# 6.net
KiCad netlist of a schematic drawn in Altium Designer
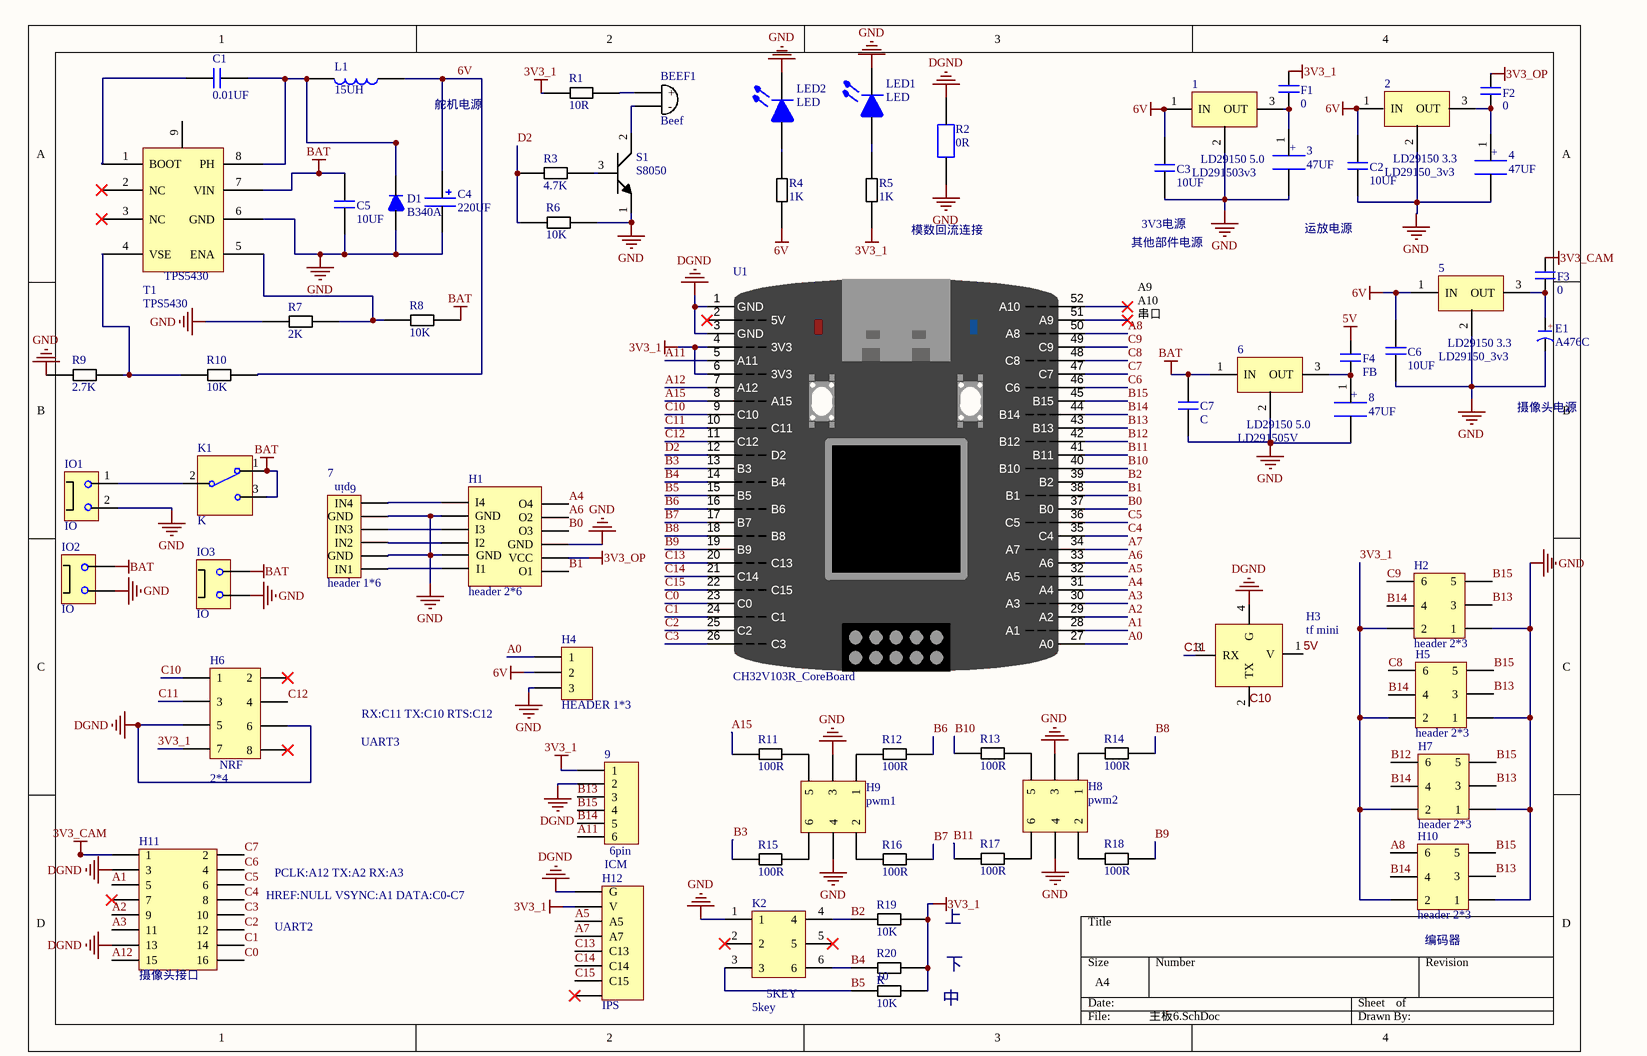
[diagram p0: 主板6.SchDoc]

(export (version "E")
  (design (tool "Eeschema 10.0.6"))
  (components
    (comp (ref "1")
      (value "LD291503v3")
      (footprint "LD29150")
      (description "5v转压")
      (libsource (lib "主板4") (part "LD291505V"))
    )
    (comp (ref "2")
      (value "LD29150_3v3")
      (footprint "LD29150")
      (description "转压3v3")
      (libsource (lib "主板4") (part "LD29150_3v3"))
    )
    (comp (ref "3") (value "47UF") (footprint "CD A(3216)") (libsource (lib "主板4") (part "钽电容")))
    (comp (ref "4") (value "47UF") (footprint "CD A(3216)") (libsource (lib "主板4") (part "钽电容")))
    (comp (ref "5")
      (value "LD29150_3v3")
      (footprint "LD29150")
      (description "转压3v3")
      (libsource (lib "主板4") (part "LD29150_3v3"))
    )
    (comp (ref "6")
      (value "LD291505V")
      (footprint "LD29150")
      (description "5v转压")
      (libsource (lib "主板6") (part "LD291505V"))
    )
    (comp (ref "7")
      (value "header 1*6")
      (footprint "HDR2.54-LI-6P")
      (description "ICM")
      (libsource (lib "") (part "header 1*6_1"))
    )
    (comp (ref "8") (value "47UF") (footprint "CD A(3216)") (libsource (lib "主板4") (part "钽电容")))
    (comp (ref "9") (value "ICM") (footprint "HDR2.54-LI-6P") (libsource (lib "主板4") (part "header 1*6")))
    (comp (ref "10") (value "10K") (footprint "0603-R") (description "电阻") (libsource (lib "主板4") (part "R")))
    (comp (ref "BEEF1")
      (value "Beef")
      (footprint "BEEF")
      (description "蜂鸣器")
      (libsource (lib "主板4") (part "Beef"))
    )
    (comp (ref "C1")
      (value "0.01UF")
      (footprint "C 0603_L")
      (description "陶瓷电容")
      (libsource (lib "主板4") (part "C"))
    )
    (comp (ref "C2")
      (value "10UF")
      (footprint "C 0603_L")
      (description "陶瓷电容")
      (libsource (lib "主板4") (part "C"))
    )
    (comp (ref "C3")
      (value "10UF")
      (footprint "C 0603_L")
      (description "陶瓷电容")
      (libsource (lib "主板4") (part "C"))
    )
    (comp (ref "C4")
      (value "220UF")
      (footprint "CAP 2.5*6.3*7")
      (description "有极电容")
      (libsource (lib "主板4") (part "C+"))
    )
    (comp (ref "C5")
      (value "10UF")
      (footprint "C 0603_L")
      (description "陶瓷电容")
      (libsource (lib "主板4") (part "C"))
    )
    (comp (ref "C6")
      (value "10UF")
      (footprint "C 0603_L")
      (description "陶瓷电容")
      (libsource (lib "主板4") (part "C"))
    )
    (comp (ref "C7")
      (value "C")
      (footprint "C 0603_L")
      (description "陶瓷电容")
      (libsource (lib "主板6") (part "C"))
    )
    (comp (ref "D1") (value "B340A") (footprint "SMA") (description "二极管") (libsource (lib "主板4") (part "D")))
    (comp (ref "E1")
      (value "A476C")
      (footprint "CD A(3216)")
      (description "贴片钽电容")
      (fields (field (name "版权归属") "源创客"))
      (libsource (lib "3.1   - 电阻-电容-电感") (part "C-CD"))
    )
    (comp (ref "F1")
      (value "0")
      (footprint "0603-C")
      (description "0欧磁珠")
      (libsource (lib "主板4") (part "FB"))
    )
    (comp (ref "F2")
      (value "0")
      (footprint "0603-C")
      (description "0欧磁珠")
      (libsource (lib "主板4") (part "FB"))
    )
    (comp (ref "F3")
      (value "0")
      (footprint "0603-C")
      (description "0欧磁珠")
      (libsource (lib "主板4") (part "FB"))
    )
    (comp (ref "F4")
      (value "FB")
      (footprint "0603-C")
      (description "0欧磁珠")
      (libsource (lib "主板6") (part "FB"))
    )
    (comp (ref "H1")
      (value "header 2*6")
      (footprint "OP")
      (description "运放接口")
      (libsource (lib "主板4") (part "header 2*6"))
    )
    (comp (ref "H2")
      (value "header 2*3")
      (footprint "HDR2.54-LI-2x3P")
      (description "编码器，PWM")
      (libsource (lib "") (part "header 2*3_1"))
    )
    (comp (ref "H3")
      (value "tf mini")
      (footprint "GH1.25")
      (description "TF MINI")
      (libsource (lib "主板6") (part "HEADER 4"))
    )
    (comp (ref "H4")
      (value "HEADER 1*3")
      (footprint "HDR2.54-LI-3P")
      (description "舵机")
      (libsource (lib "主板4") (part "HEADER 1*3"))
    )
    (comp (ref "H5")
      (value "header 2*3")
      (footprint "HDR2.54-LI-2x3P")
      (description "编码器，PWM")
      (libsource (lib "") (part "header 2*3_1"))
    )
    (comp (ref "H6")
      (value "2*4")
      (footprint "HDR2.54-LI-2x4P")
      (description "NRF")
      (libsource (lib "主板4") (part "2*4"))
    )
    (comp (ref "H7")
      (value "header 2*3")
      (footprint "HDR2.54-LI-2x3P")
      (description "编码器，PWM")
      (libsource (lib "") (part "header 2*3_1"))
    )
    (comp (ref "H8")
      (value "pwm2")
      (footprint "HDR2.54-LI-2x3P")
      (description "编码器，PWM")
      (libsource (lib "主板4") (part "header 2*3"))
    )
    (comp (ref "H9")
      (value "pwm1")
      (footprint "HDR2.54-LI-2x3P")
      (description "编码器，PWM")
      (libsource (lib "主板4") (part "header 2*3"))
    )
    (comp (ref "H10")
      (value "header 2*3")
      (footprint "HDR2.54-LI-2x3P")
      (description "编码器，PWM")
      (libsource (lib "") (part "header 2*3_1"))
    )
    (comp (ref "H11")
      (value "摄像头接口")
      (footprint "HDR2.54-LI-2x8P")
      (libsource (lib "主板4") (part "Header 2*8"))
    )
    (comp (ref "H12")
      (value "IPS")
      (footprint "HDR2.54-M-LI-8P")
      (description "屏幕")
      (libsource (lib "主板5") (part "HEADER 8"))
    )
    (comp (ref "IO1") (value "IO") (footprint "XT30") (description "接口") (libsource (lib "主板4") (part "IO")))
    (comp (ref "IO2") (value "IO") (footprint "XT30") (description "接口") (libsource (lib "") (part "IO_1")))
    (comp (ref "IO3") (value "IO") (footprint "XT30") (description "接口") (libsource (lib "") (part "IO_1")))
    (comp (ref "K1")
      (value "K")
      (footprint "SW-SPDT-3A250V")
      (description "开关")
      (libsource (lib "主板4") (part "K"))
    )
    (comp (ref "K2")
      (value "5key")
      (footprint "5KEY")
      (description "5Key")
      (libsource (lib "主板4") (part "5key"))
    )
    (comp (ref "L1")
      (value "15UH")
      (footprint "L-SMD-7")
      (description "电感")
      (libsource (lib "主板4") (part "L"))
    )
    (comp (ref "LED1") (value "LED") (footprint "0603-LED-R") (libsource (lib "主板4") (part "LED")))
    (comp (ref "LED2") (value "LED") (footprint "0603-LED-R") (libsource (lib "主板4") (part "LED")))
    (comp (ref "R1") (value "10R") (footprint "0603-R") (description "电阻") (libsource (lib "主板4") (part "R")))
    (comp (ref "R2")
      (value "0R")
      (footprint "0603-C")
      (description "0欧电阻")
      (libsource (lib "主板4") (part "R0"))
    )
    (comp (ref "R3")
      (value "4.7K")
      (footprint "0603-R")
      (description "电阻")
      (libsource (lib "主板4") (part "R"))
    )
    (comp (ref "R4") (value "1K") (footprint "0603-R") (description "电阻") (libsource (lib "主板4") (part "R")))
    (comp (ref "R5") (value "1K") (footprint "0603-R") (description "电阻") (libsource (lib "主板4") (part "R")))
    (comp (ref "R6") (value "10K") (footprint "0603-R") (description "电阻") (libsource (lib "主板4") (part "R")))
    (comp (ref "R7") (value "2K") (footprint "0603-R") (description "电阻") (libsource (lib "主板4") (part "R")))
    (comp (ref "R8") (value "10K") (footprint "0603-R") (description "电阻") (libsource (lib "主板4") (part "R")))
    (comp (ref "R9")
      (value "2.7K")
      (footprint "0603-R")
      (description "电阻")
      (libsource (lib "主板4") (part "R"))
    )
    (comp (ref "R10")
      (value "10K")
      (footprint "0603-R")
      (description "电阻")
      (libsource (lib "主板4") (part "R"))
    )
    (comp (ref "R11")
      (value "100R")
      (footprint "0603-R")
      (description "电阻")
      (libsource (lib "主板4") (part "R"))
    )
    (comp (ref "R12")
      (value "100R")
      (footprint "0603-R")
      (description "电阻")
      (libsource (lib "主板4") (part "R"))
    )
    (comp (ref "R13")
      (value "100R")
      (footprint "0603-R")
      (description "电阻")
      (libsource (lib "主板4") (part "R"))
    )
    (comp (ref "R14")
      (value "100R")
      (footprint "0603-R")
      (description "电阻")
      (libsource (lib "主板4") (part "R"))
    )
    (comp (ref "R15")
      (value "100R")
      (footprint "0603-R")
      (description "电阻")
      (libsource (lib "主板4") (part "R"))
    )
    (comp (ref "R16")
      (value "100R")
      (footprint "0603-R")
      (description "电阻")
      (libsource (lib "主板4") (part "R"))
    )
    (comp (ref "R17")
      (value "100R")
      (footprint "0603-R")
      (description "电阻")
      (libsource (lib "主板4") (part "R"))
    )
    (comp (ref "R18")
      (value "100R")
      (footprint "0603-R")
      (description "电阻")
      (libsource (lib "主板4") (part "R"))
    )
    (comp (ref "R19")
      (value "10K")
      (footprint "0603-R")
      (description "电阻")
      (libsource (lib "主板4") (part "R"))
    )
    (comp (ref "R20") (value "R") (footprint "0603-R") (description "电阻") (libsource (lib "主板4") (part "R")))
    (comp (ref "S1")
      (value "S8050")
      (footprint "SOT-23-3_L2.9-W1.3-P1.90-LS2.4-BR - duplicate")
      (description "三极管")
      (libsource (lib "主板4") (part "S8050"))
    )
    (comp (ref "T1")
      (value "TPS5430")
      (footprint "TPS5430")
      (description "转压8转6v")
      (libsource (lib "主板4") (part "TPS5430"))
    )
    (comp (ref "U1")
      (value "CH32V103R_CoreBoard")
      (footprint "CH32V103R_CoreBoard")
      (description "逐飞科技 CH32V103R核心板")
      (libsource (lib "主板4") (part "CH32V103R_CoreBoard"))
    )
  )
  (nets
    (net (code "1") (name "/A0") (class "Default")
      (node (ref "H4") (pin "1") (pinfunction "1_1") (pintype "passive"))
      (node (ref "U1") (pin "27") (pinfunction "A0_27") (pintype "passive"))
    )
    (net (code "2") (name "/A1") (class "Default")
      (node (ref "H11") (pin "5") (pinfunction "5_5") (pintype "passive"))
      (node (ref "U1") (pin "28") (pinfunction "A1_28") (pintype "passive"))
    )
    (net (code "3") (name "/A2") (class "Default")
      (node (ref "H11") (pin "9") (pinfunction "9_9") (pintype "passive"))
      (node (ref "U1") (pin "29") (pinfunction "A2_29") (pintype "passive"))
    )
    (net (code "4") (name "/A3") (class "Default")
      (node (ref "H11") (pin "11") (pinfunction "11_11") (pintype "passive"))
      (node (ref "U1") (pin "30") (pinfunction "A3_30") (pintype "passive"))
    )
    (net (code "5") (name "/A4") (class "Default")
      (node (ref "H1") (pin "12") (pinfunction "O4_12") (pintype "passive"))
      (node (ref "U1") (pin "31") (pinfunction "A4_31") (pintype "passive"))
    )
    (net (code "6") (name "/A5") (class "Default")
      (node (ref "H12") (pin "3") (pinfunction "A5_3") (pintype "passive"))
      (node (ref "U1") (pin "32") (pinfunction "A5_32") (pintype "passive"))
    )
    (net (code "7") (name "/A6") (class "Default")
      (node (ref "H1") (pin "10") (pinfunction "O2_10") (pintype "passive"))
      (node (ref "U1") (pin "33") (pinfunction "A6_33") (pintype "passive"))
    )
    (net (code "8") (name "/A7") (class "Default")
      (node (ref "H12") (pin "4") (pinfunction "A7_4") (pintype "passive"))
      (node (ref "U1") (pin "34") (pinfunction "A7_34") (pintype "passive"))
    )
    (net (code "9") (name "/A8") (class "Default")
      (node (ref "H10") (pin "6") (pinfunction "6_6") (pintype "passive"))
      (node (ref "U1") (pin "50") (pinfunction "A8_50") (pintype "passive"))
    )
    (net (code "10") (name "/A11") (class "Default")
      (node (ref "9") (pin "6") (pinfunction "6_6") (pintype "passive"))
      (node (ref "U1") (pin "5") (pinfunction "A11_5") (pintype "passive"))
    )
    (net (code "11") (name "/A12") (class "Default")
      (node (ref "H11") (pin "15") (pinfunction "15_15") (pintype "passive"))
      (node (ref "U1") (pin "7") (pinfunction "A12_7") (pintype "passive"))
    )
    (net (code "12") (name "/A15") (class "Default")
      (node (ref "R11") (pin "1") (pinfunction "1_1") (pintype "passive"))
      (node (ref "U1") (pin "8") (pinfunction "A15_8") (pintype "passive"))
    )
    (net (code "13") (name "/B0") (class "Default")
      (node (ref "H1") (pin "11") (pinfunction "O3_11") (pintype "passive"))
      (node (ref "U1") (pin "37") (pinfunction "B0_37") (pintype "passive"))
    )
    (net (code "14") (name "/B1") (class "Default")
      (node (ref "H1") (pin "7") (pinfunction "O1_7") (pintype "passive"))
      (node (ref "U1") (pin "38") (pinfunction "B1_38") (pintype "passive"))
    )
    (net (code "15") (name "/B2") (class "Default")
      (node (ref "K2") (pin "4") (pinfunction "4_4") (pintype "passive"))
      (node (ref "R19") (pin "1") (pinfunction "1_1") (pintype "passive"))
      (node (ref "U1") (pin "39") (pinfunction "B2_39") (pintype "passive"))
    )
    (net (code "16") (name "/B3") (class "Default")
      (node (ref "R15") (pin "1") (pinfunction "1_1") (pintype "passive"))
      (node (ref "U1") (pin "13") (pinfunction "B3_13") (pintype "passive"))
    )
    (net (code "17") (name "/B4") (class "Default")
      (node (ref "K2") (pin "6") (pinfunction "6_6") (pintype "passive"))
      (node (ref "R20") (pin "1") (pinfunction "1_1") (pintype "passive"))
      (node (ref "U1") (pin "14") (pinfunction "B4_14") (pintype "passive"))
    )
    (net (code "18") (name "/B5") (class "Default")
      (node (ref "10") (pin "1") (pinfunction "1_1") (pintype "passive"))
      (node (ref "K2") (pin "3") (pinfunction "3_3") (pintype "passive"))
      (node (ref "U1") (pin "15") (pinfunction "B5_15") (pintype "passive"))
    )
    (net (code "19") (name "/B6") (class "Default")
      (node (ref "R12") (pin "2") (pinfunction "2_2") (pintype "passive"))
      (node (ref "U1") (pin "16") (pinfunction "B6_16") (pintype "passive"))
    )
    (net (code "20") (name "/B7") (class "Default")
      (node (ref "R16") (pin "2") (pinfunction "2_2") (pintype "passive"))
      (node (ref "U1") (pin "17") (pinfunction "B7_17") (pintype "passive"))
    )
    (net (code "21") (name "/B8") (class "Default")
      (node (ref "R14") (pin "2") (pinfunction "2_2") (pintype "passive"))
      (node (ref "U1") (pin "18") (pinfunction "B8_18") (pintype "passive"))
    )
    (net (code "22") (name "/B9") (class "Default")
      (node (ref "R18") (pin "2") (pinfunction "2_2") (pintype "passive"))
      (node (ref "U1") (pin "19") (pinfunction "B9_19") (pintype "passive"))
    )
    (net (code "23") (name "/B10") (class "Default")
      (node (ref "R13") (pin "1") (pinfunction "1_1") (pintype "passive"))
      (node (ref "U1") (pin "40") (pinfunction "B10_40") (pintype "passive"))
    )
    (net (code "24") (name "/B11") (class "Default")
      (node (ref "R17") (pin "1") (pinfunction "1_1") (pintype "passive"))
      (node (ref "U1") (pin "41") (pinfunction "B11_41") (pintype "passive"))
    )
    (net (code "25") (name "/B12") (class "Default")
      (node (ref "H7") (pin "6") (pinfunction "6_6") (pintype "passive"))
      (node (ref "U1") (pin "42") (pinfunction "B12_42") (pintype "passive"))
    )
    (net (code "26") (name "/B13") (class "Default")
      (node (ref "9") (pin "3") (pinfunction "3_3") (pintype "passive"))
      (node (ref "H10") (pin "3") (pinfunction "3_3") (pintype "passive"))
      (node (ref "H2") (pin "3") (pinfunction "3_3") (pintype "passive"))
      (node (ref "H5") (pin "3") (pinfunction "3_3") (pintype "passive"))
      (node (ref "H7") (pin "3") (pinfunction "3_3") (pintype "passive"))
      (node (ref "U1") (pin "43") (pinfunction "B13_43") (pintype "passive"))
    )
    (net (code "27") (name "/B14") (class "Default")
      (node (ref "9") (pin "5") (pinfunction "5_5") (pintype "passive"))
      (node (ref "H10") (pin "4") (pinfunction "4_4") (pintype "passive"))
      (node (ref "H2") (pin "4") (pinfunction "4_4") (pintype "passive"))
      (node (ref "H5") (pin "4") (pinfunction "4_4") (pintype "passive"))
      (node (ref "H7") (pin "4") (pinfunction "4_4") (pintype "passive"))
      (node (ref "U1") (pin "44") (pinfunction "B14_44") (pintype "passive"))
    )
    (net (code "28") (name "/B15") (class "Default")
      (node (ref "9") (pin "4") (pinfunction "4_4") (pintype "passive"))
      (node (ref "H10") (pin "5") (pinfunction "5_5") (pintype "passive"))
      (node (ref "H2") (pin "5") (pinfunction "5_5") (pintype "passive"))
      (node (ref "H5") (pin "5") (pinfunction "5_5") (pintype "passive"))
      (node (ref "H7") (pin "5") (pinfunction "5_5") (pintype "passive"))
      (node (ref "U1") (pin "45") (pinfunction "B15_45") (pintype "passive"))
    )
    (net (code "29") (name "/C0") (class "Default")
      (node (ref "H11") (pin "16") (pinfunction "16_16") (pintype "passive"))
      (node (ref "U1") (pin "23") (pinfunction "C0_23") (pintype "passive"))
    )
    (net (code "30") (name "/C1") (class "Default")
      (node (ref "H11") (pin "14") (pinfunction "14_14") (pintype "passive"))
      (node (ref "U1") (pin "24") (pinfunction "C1_24") (pintype "passive"))
    )
    (net (code "31") (name "/C2") (class "Default")
      (node (ref "H11") (pin "12") (pinfunction "12_12") (pintype "passive"))
      (node (ref "U1") (pin "25") (pinfunction "C2_25") (pintype "passive"))
    )
    (net (code "32") (name "/C3") (class "Default")
      (node (ref "H11") (pin "10") (pinfunction "10_10") (pintype "passive"))
      (node (ref "U1") (pin "26") (pinfunction "C3_26") (pintype "passive"))
    )
    (net (code "33") (name "/C4") (class "Default")
      (node (ref "H11") (pin "8") (pinfunction "8_8") (pintype "passive"))
      (node (ref "U1") (pin "35") (pinfunction "C4_35") (pintype "passive"))
    )
    (net (code "34") (name "/C5") (class "Default")
      (node (ref "H11") (pin "6") (pinfunction "6_6") (pintype "passive"))
      (node (ref "U1") (pin "36") (pinfunction "C5_36") (pintype "passive"))
    )
    (net (code "35") (name "/C6") (class "Default")
      (node (ref "H11") (pin "4") (pinfunction "4_4") (pintype "passive"))
      (node (ref "U1") (pin "46") (pinfunction "C6_46") (pintype "passive"))
    )
    (net (code "36") (name "/C7") (class "Default")
      (node (ref "H11") (pin "2") (pinfunction "2_2") (pintype "passive"))
      (node (ref "U1") (pin "47") (pinfunction "C7_47") (pintype "passive"))
    )
    (net (code "37") (name "/C8") (class "Default")
      (node (ref "H5") (pin "6") (pinfunction "6_6") (pintype "passive"))
      (node (ref "U1") (pin "48") (pinfunction "C8_48") (pintype "passive"))
    )
    (net (code "38") (name "/C9") (class "Default")
      (node (ref "H2") (pin "6") (pinfunction "6_6") (pintype "passive"))
      (node (ref "U1") (pin "49") (pinfunction "C9_49") (pintype "passive"))
    )
    (net (code "39") (name "/C10") (class "Default")
      (node (ref "H3") (pin "2") (pinfunction "TX_2") (pintype "passive"))
      (node (ref "H6") (pin "1") (pinfunction "1_1") (pintype "passive"))
      (node (ref "U1") (pin "9") (pinfunction "C10_9") (pintype "passive"))
    )
    (net (code "40") (name "/C11") (class "Default")
      (node (ref "H3") (pin "3") (pinfunction "RX_3") (pintype "passive"))
      (node (ref "H6") (pin "3") (pinfunction "3_3") (pintype "passive"))
      (node (ref "U1") (pin "10") (pinfunction "C11_10") (pintype "passive"))
    )
    (net (code "41") (name "/C12") (class "Default")
      (node (ref "H6") (pin "4") (pinfunction "4_4") (pintype "passive"))
      (node (ref "U1") (pin "11") (pinfunction "C12_11") (pintype "passive"))
    )
    (net (code "42") (name "/C13") (class "Default")
      (node (ref "H12") (pin "5") (pinfunction "C13_5") (pintype "passive"))
      (node (ref "U1") (pin "20") (pinfunction "C13_20") (pintype "passive"))
    )
    (net (code "43") (name "/C14") (class "Default")
      (node (ref "H12") (pin "6") (pinfunction "C14_6") (pintype "passive"))
      (node (ref "U1") (pin "21") (pinfunction "C14_21") (pintype "passive"))
    )
    (net (code "44") (name "/C15") (class "Default")
      (node (ref "H12") (pin "7") (pinfunction "C15_7") (pintype "passive"))
      (node (ref "U1") (pin "22") (pinfunction "C15_22") (pintype "passive"))
    )
    (net (code "45") (name "/D2") (class "Default")
      (node (ref "R3") (pin "1") (pinfunction "1_1") (pintype "passive"))
      (node (ref "R6") (pin "1") (pinfunction "1_1") (pintype "passive"))
      (node (ref "U1") (pin "12") (pinfunction "D2_12") (pintype "passive"))
    )
    (net (code "46") (name "3V3_1") (class "Default")
      (node (ref "10") (pin "2") (pinfunction "2_2") (pintype "passive"))
      (node (ref "9") (pin "1") (pinfunction "1_1") (pintype "passive"))
      (node (ref "F1") (pin "2") (pinfunction "2_2") (pintype "passive"))
      (node (ref "H10") (pin "2") (pinfunction "2_2") (pintype "passive"))
      (node (ref "H12") (pin "2") (pinfunction "V_2") (pintype "passive"))
      (node (ref "H2") (pin "2") (pinfunction "2_2") (pintype "passive"))
      (node (ref "H5") (pin "2") (pinfunction "2_2") (pintype "passive"))
      (node (ref "H6") (pin "7") (pinfunction "7_7") (pintype "passive"))
      (node (ref "H7") (pin "2") (pinfunction "2_2") (pintype "passive"))
      (node (ref "R1") (pin "1") (pinfunction "1_1") (pintype "passive"))
      (node (ref "R19") (pin "2") (pinfunction "2_2") (pintype "passive"))
      (node (ref "R20") (pin "2") (pinfunction "2_2") (pintype "passive"))
      (node (ref "R5") (pin "1") (pinfunction "1_1") (pintype "passive"))
      (node (ref "U1") (pin "4") (pinfunction "3V3_4") (pintype "passive"))
      (node (ref "U1") (pin "6") (pinfunction "3V3_6") (pintype "passive"))
    )
    (net (code "47") (name "3V3_CAM") (class "Default")
      (node (ref "F3") (pin "1") (pinfunction "1_1") (pintype "passive"))
      (node (ref "H11") (pin "1") (pinfunction "1_1") (pintype "passive"))
    )
    (net (code "48") (name "3V3_OP") (class "Default")
      (node (ref "F2") (pin "1") (pinfunction "1_1") (pintype "passive"))
      (node (ref "H1") (pin "8") (pinfunction "VCC_8") (pintype "passive"))
    )
    (net (code "49") (name "5V") (class "Default")
      (node (ref "F4") (pin "2") (pinfunction "2_2") (pintype "passive"))
      (node (ref "H3") (pin "1") (pinfunction "V_1") (pintype "passive"))
    )
    (net (code "50") (name "6V") (class "Default")
      (node (ref "1") (pin "1") (pinfunction "IN_1") (pintype "passive"))
      (node (ref "2") (pin "1") (pinfunction "IN_1") (pintype "passive"))
      (node (ref "5") (pin "1") (pinfunction "IN_1") (pintype "passive"))
      (node (ref "C2") (pin "2") (pinfunction "2_2") (pintype "passive"))
      (node (ref "C3") (pin "1") (pinfunction "1_1") (pintype "passive"))
      (node (ref "C4") (pin "1") (pinfunction "1_1") (pintype "passive"))
      (node (ref "C6") (pin "2") (pinfunction "2_2") (pintype "passive"))
      (node (ref "H4") (pin "2") (pinfunction "2_2") (pintype "passive"))
      (node (ref "L1") (pin "2") (pinfunction "2_2") (pintype "passive"))
      (node (ref "R10") (pin "2") (pinfunction "2_2") (pintype "passive"))
      (node (ref "R4") (pin "1") (pinfunction "1_1") (pintype "passive"))
    )
    (net (code "51") (name "BAT") (class "Default")
      (node (ref "6") (pin "1") (pinfunction "IN_1") (pintype "passive"))
      (node (ref "C5") (pin "2") (pinfunction "2_2") (pintype "passive"))
      (node (ref "C7") (pin "2") (pinfunction "2_2") (pintype "passive"))
      (node (ref "IO2") (pin "1") (pinfunction "1_1") (pintype "passive"))
      (node (ref "IO3") (pin "1") (pinfunction "1_1") (pintype "passive"))
      (node (ref "K1") (pin "1") (pinfunction "1_1") (pintype "passive"))
      (node (ref "K1") (pin "3") (pinfunction "3_3") (pintype "passive"))
      (node (ref "R8") (pin "2") (pinfunction "2_2") (pintype "passive"))
      (node (ref "T1") (pin "7") (pinfunction "VIN_7") (pintype "passive"))
    )
    (net (code "52") (name "DGND") (class "Default")
      (node (ref "9") (pin "2") (pinfunction "2_2") (pintype "passive"))
      (node (ref "H11") (pin "13") (pinfunction "13_13") (pintype "passive"))
      (node (ref "H11") (pin "3") (pinfunction "3_3") (pintype "passive"))
      (node (ref "H12") (pin "1") (pinfunction "G_1") (pintype "passive"))
      (node (ref "H3") (pin "4") (pinfunction "G_4") (pintype "passive"))
      (node (ref "H6") (pin "5") (pinfunction "5_5") (pintype "passive"))
      (node (ref "H6") (pin "6") (pinfunction "6_6") (pintype "passive"))
      (node (ref "R2") (pin "2") (pinfunction "2_2") (pintype "passive"))
      (node (ref "U1") (pin "1") (pinfunction "GND_1") (pintype "passive"))
      (node (ref "U1") (pin "3") (pinfunction "GND_3") (pintype "passive"))
    )
    (net (code "53") (name "GND") (class "Default")
      (node (ref "1") (pin "2") (pinfunction "GND_2") (pintype "passive"))
      (node (ref "2") (pin "2") (pinfunction "GND_2") (pintype "passive"))
      (node (ref "3") (pin "2") (pinfunction "2_2") (pintype "passive"))
      (node (ref "4") (pin "2") (pinfunction "2_2") (pintype "passive"))
      (node (ref "5") (pin "2") (pinfunction "GND_2") (pintype "passive"))
      (node (ref "6") (pin "2") (pinfunction "GND_2") (pintype "passive"))
      (node (ref "7") (pin "2") (pinfunction "GND_2") (pintype "passive"))
      (node (ref "7") (pin "5") (pinfunction "GND_5") (pintype "passive"))
      (node (ref "8") (pin "2") (pinfunction "2_2") (pintype "passive"))
      (node (ref "C2") (pin "1") (pinfunction "1_1") (pintype "passive"))
      (node (ref "C3") (pin "2") (pinfunction "2_2") (pintype "passive"))
      (node (ref "C4") (pin "2") (pinfunction "2_2") (pintype "passive"))
      (node (ref "C5") (pin "1") (pinfunction "1_1") (pintype "passive"))
      (node (ref "C6") (pin "1") (pinfunction "1_1") (pintype "passive"))
      (node (ref "C7") (pin "1") (pinfunction "1_1") (pintype "passive"))
      (node (ref "D1") (pin "1") (pinfunction "A_1") (pintype "passive"))
      (node (ref "E1") (pin "2") (pinfunction "K_2") (pintype "passive"))
      (node (ref "H1") (pin "2") (pinfunction "GND_2") (pintype "passive"))
      (node (ref "H1") (pin "5") (pinfunction "GND_5") (pintype "passive"))
      (node (ref "H1") (pin "9") (pinfunction "GND_9") (pintype "passive"))
      (node (ref "H10") (pin "1") (pinfunction "1_1") (pintype "passive"))
      (node (ref "H2") (pin "1") (pinfunction "1_1") (pintype "passive"))
      (node (ref "H4") (pin "3") (pinfunction "3_3") (pintype "passive"))
      (node (ref "H5") (pin "1") (pinfunction "1_1") (pintype "passive"))
      (node (ref "H7") (pin "1") (pinfunction "1_1") (pintype "passive"))
      (node (ref "H8") (pin "3") (pinfunction "3_3") (pintype "passive"))
      (node (ref "H8") (pin "4") (pinfunction "4_4") (pintype "passive"))
      (node (ref "H9") (pin "3") (pinfunction "3_3") (pintype "passive"))
      (node (ref "H9") (pin "4") (pinfunction "4_4") (pintype "passive"))
      (node (ref "IO1") (pin "2") (pinfunction "2_2") (pintype "passive"))
      (node (ref "IO2") (pin "2") (pinfunction "2_2") (pintype "passive"))
      (node (ref "IO3") (pin "2") (pinfunction "2_2") (pintype "passive"))
      (node (ref "K2") (pin "1") (pinfunction "1_1") (pintype "passive"))
      (node (ref "LED1") (pin "LED-") (pinfunction "2_LED-") (pintype "passive"))
      (node (ref "LED2") (pin "LED-") (pinfunction "2_LED-") (pintype "passive"))
      (node (ref "R2") (pin "1") (pinfunction "1_1") (pintype "passive"))
      (node (ref "R6") (pin "2") (pinfunction "2_2") (pintype "passive"))
      (node (ref "R7") (pin "1") (pinfunction "1_1") (pintype "passive"))
      (node (ref "R9") (pin "1") (pinfunction "1_1") (pintype "passive"))
      (node (ref "S1") (pin "1") (pinfunction "1_1") (pintype "passive"))
      (node (ref "T1") (pin "6") (pinfunction "GND_6") (pintype "passive"))
    )
    (net (code "54") (name "Net-(1-OUT)") (class "Default")
      (node (ref "1") (pin "3") (pinfunction "OUT_3") (pintype "passive"))
      (node (ref "3") (pin "1") (pinfunction "+_1") (pintype "passive"))
      (node (ref "F1") (pin "1") (pinfunction "1_1") (pintype "passive"))
    )
    (net (code "55") (name "Net-(2-OUT)") (class "Default")
      (node (ref "2") (pin "3") (pinfunction "OUT_3") (pintype "passive"))
      (node (ref "4") (pin "1") (pinfunction "+_1") (pintype "passive"))
      (node (ref "F2") (pin "2") (pinfunction "2_2") (pintype "passive"))
    )
    (net (code "56") (name "Net-(5-OUT)") (class "Default")
      (node (ref "5") (pin "3") (pinfunction "OUT_3") (pintype "passive"))
      (node (ref "E1") (pin "1") (pinfunction "A_1") (pintype "passive"))
      (node (ref "F3") (pin "2") (pinfunction "2_2") (pintype "passive"))
    )
    (net (code "57") (name "Net-(6-OUT)") (class "Default")
      (node (ref "6") (pin "3") (pinfunction "OUT_3") (pintype "passive"))
      (node (ref "8") (pin "1") (pinfunction "+_1") (pintype "passive"))
      (node (ref "F4") (pin "1") (pinfunction "1_1") (pintype "passive"))
    )
    (net (code "58") (name "Net-(7-IN1)") (class "Default")
      (node (ref "7") (pin "1") (pinfunction "IN1_1") (pintype "passive"))
      (node (ref "H1") (pin "6") (pinfunction "I1_6") (pintype "passive"))
    )
    (net (code "59") (name "Net-(7-IN2)") (class "Default")
      (node (ref "7") (pin "3") (pinfunction "IN2_3") (pintype "passive"))
      (node (ref "H1") (pin "4") (pinfunction "I2_4") (pintype "passive"))
    )
    (net (code "60") (name "Net-(7-IN3)") (class "Default")
      (node (ref "7") (pin "4") (pinfunction "IN3_4") (pintype "passive"))
      (node (ref "H1") (pin "3") (pinfunction "I3_3") (pintype "passive"))
    )
    (net (code "61") (name "Net-(7-IN4)") (class "Default")
      (node (ref "7") (pin "6") (pinfunction "IN4_6") (pintype "passive"))
      (node (ref "H1") (pin "1") (pinfunction "I4_1") (pintype "passive"))
    )
    (net (code "62") (name "Net-(BEEF1-+)") (class "Default")
      (node (ref "BEEF1") (pin "1") (pinfunction "+_1") (pintype "passive"))
      (node (ref "R1") (pin "2") (pinfunction "2_2") (pintype "passive"))
    )
    (net (code "63") (name "Net-(BEEF1--)") (class "Default")
      (node (ref "BEEF1") (pin "2") (pinfunction "-_2") (pintype "passive"))
      (node (ref "S1") (pin "2") (pinfunction "2_2") (pintype "passive"))
    )
    (net (code "64") (name "Net-(D1-K)") (class "Default")
      (node (ref "C1") (pin "2") (pinfunction "2_2") (pintype "passive"))
      (node (ref "D1") (pin "2") (pinfunction "K_2") (pintype "passive"))
      (node (ref "L1") (pin "1") (pinfunction "1_1") (pintype "passive"))
      (node (ref "T1") (pin "8") (pinfunction "PH_8") (pintype "passive"))
    )
    (net (code "65") (name "Net-(H8-Pad1)") (class "Default")
      (node (ref "H8") (pin "1") (pinfunction "1_1") (pintype "passive"))
      (node (ref "R14") (pin "1") (pinfunction "1_1") (pintype "passive"))
    )
    (net (code "66") (name "Net-(H8-Pad2)") (class "Default")
      (node (ref "H8") (pin "2") (pinfunction "2_2") (pintype "passive"))
      (node (ref "R18") (pin "1") (pinfunction "1_1") (pintype "passive"))
    )
    (net (code "67") (name "Net-(H8-Pad5)") (class "Default")
      (node (ref "H8") (pin "5") (pinfunction "5_5") (pintype "passive"))
      (node (ref "R13") (pin "2") (pinfunction "2_2") (pintype "passive"))
    )
    (net (code "68") (name "Net-(H8-Pad6)") (class "Default")
      (node (ref "H8") (pin "6") (pinfunction "6_6") (pintype "passive"))
      (node (ref "R17") (pin "2") (pinfunction "2_2") (pintype "passive"))
    )
    (net (code "69") (name "Net-(H9-Pad1)") (class "Default")
      (node (ref "H9") (pin "1") (pinfunction "1_1") (pintype "passive"))
      (node (ref "R12") (pin "1") (pinfunction "1_1") (pintype "passive"))
    )
    (net (code "70") (name "Net-(H9-Pad2)") (class "Default")
      (node (ref "H9") (pin "2") (pinfunction "2_2") (pintype "passive"))
      (node (ref "R16") (pin "1") (pinfunction "1_1") (pintype "passive"))
    )
    (net (code "71") (name "Net-(H9-Pad5)") (class "Default")
      (node (ref "H9") (pin "5") (pinfunction "5_5") (pintype "passive"))
      (node (ref "R11") (pin "2") (pinfunction "2_2") (pintype "passive"))
    )
    (net (code "72") (name "Net-(H9-Pad6)") (class "Default")
      (node (ref "H9") (pin "6") (pinfunction "6_6") (pintype "passive"))
      (node (ref "R15") (pin "2") (pinfunction "2_2") (pintype "passive"))
    )
    (net (code "73") (name "Net-(IO1-Pad1)") (class "Default")
      (node (ref "IO1") (pin "1") (pinfunction "1_1") (pintype "passive"))
      (node (ref "K1") (pin "2") (pinfunction "2_2") (pintype "passive"))
    )
    (net (code "74") (name "Net-(LED1-1)") (class "Default")
      (node (ref "LED1") (pin "LED+") (pinfunction "1_LED+") (pintype "passive"))
      (node (ref "R5") (pin "2") (pinfunction "2_2") (pintype "passive"))
    )
    (net (code "75") (name "Net-(LED2-1)") (class "Default")
      (node (ref "LED2") (pin "LED+") (pinfunction "1_LED+") (pintype "passive"))
      (node (ref "R4") (pin "2") (pinfunction "2_2") (pintype "passive"))
    )
    (net (code "76") (name "Net-(R3-Pad2)") (class "Default")
      (node (ref "R3") (pin "2") (pinfunction "2_2") (pintype "passive"))
      (node (ref "S1") (pin "3") (pinfunction "3_3") (pintype "passive"))
    )
    (net (code "77") (name "Net-(T1-BOOT)") (class "Default")
      (node (ref "C1") (pin "1") (pinfunction "1_1") (pintype "passive"))
      (node (ref "T1") (pin "1") (pinfunction "BOOT_1") (pintype "passive"))
    )
    (net (code "78") (name "Net-(T1-ENA)") (class "Default")
      (node (ref "R7") (pin "2") (pinfunction "2_2") (pintype "passive"))
      (node (ref "R8") (pin "1") (pinfunction "1_1") (pintype "passive"))
      (node (ref "T1") (pin "5") (pinfunction "ENA_5") (pintype "passive"))
    )
    (net (code "79") (name "Net-(T1-VSE)") (class "Default")
      (node (ref "R10") (pin "1") (pinfunction "1_1") (pintype "passive"))
      (node (ref "R9") (pin "2") (pinfunction "2_2") (pintype "passive"))
      (node (ref "T1") (pin "4") (pinfunction "VSE_4") (pintype "passive"))
    )
    (net (code "80") (name "unconnected-(H6-Pad2)") (class "Default")
      (node (ref "H6") (pin "2") (pinfunction "2_2") (pintype "passive+no_connect"))
    )
    (net (code "81") (name "unconnected-(H6-Pad8)") (class "Default")
      (node (ref "H6") (pin "8") (pinfunction "8_8") (pintype "passive+no_connect"))
    )
    (net (code "82") (name "unconnected-(H11-Pad7)") (class "Default")
      (node (ref "H11") (pin "7") (pinfunction "7_7") (pintype "passive+no_connect"))
    )
    (net (code "83") (name "unconnected-(H12-Pad8)") (class "Default")
      (node (ref "H12") (pin "8") (pintype "passive+no_connect"))
    )
    (net (code "84") (name "unconnected-(K2-Pad2)") (class "Default")
      (node (ref "K2") (pin "2") (pinfunction "2_2") (pintype "passive+no_connect"))
    )
    (net (code "85") (name "unconnected-(K2-Pad5)") (class "Default")
      (node (ref "K2") (pin "5") (pinfunction "5_5") (pintype "passive+no_connect"))
    )
    (net (code "86") (name "unconnected-(T1-NC-Pad2)") (class "Default")
      (node (ref "T1") (pin "2") (pinfunction "NC_2") (pintype "passive+no_connect"))
    )
    (net (code "87") (name "unconnected-(T1-NC-Pad3)") (class "Default")
      (node (ref "T1") (pin "3") (pinfunction "NC_3") (pintype "passive+no_connect"))
    )
    (net (code "88") (name "unconnected-(T1-Pad9)") (class "Default")
      (node (ref "T1") (pin "9") (pinfunction "9_9") (pintype "passive"))
    )
    (net (code "89") (name "unconnected-(U1-5V-Pad2)") (class "Default")
      (node (ref "U1") (pin "2") (pinfunction "5V_2") (pintype "passive+no_connect"))
    )
    (net (code "90") (name "unconnected-(U1-A9-Pad51)") (class "Default")
      (node (ref "U1") (pin "51") (pinfunction "A9_51") (pintype "passive+no_connect"))
    )
    (net (code "91") (name "unconnected-(U1-A10-Pad52)") (class "Default")
      (node (ref "U1") (pin "52") (pinfunction "A10_52") (pintype "passive+no_connect"))
    )
  )
)
